# ADC16b_Pressure.net
KiCad netlist of a schematic drawn in Altium Designer
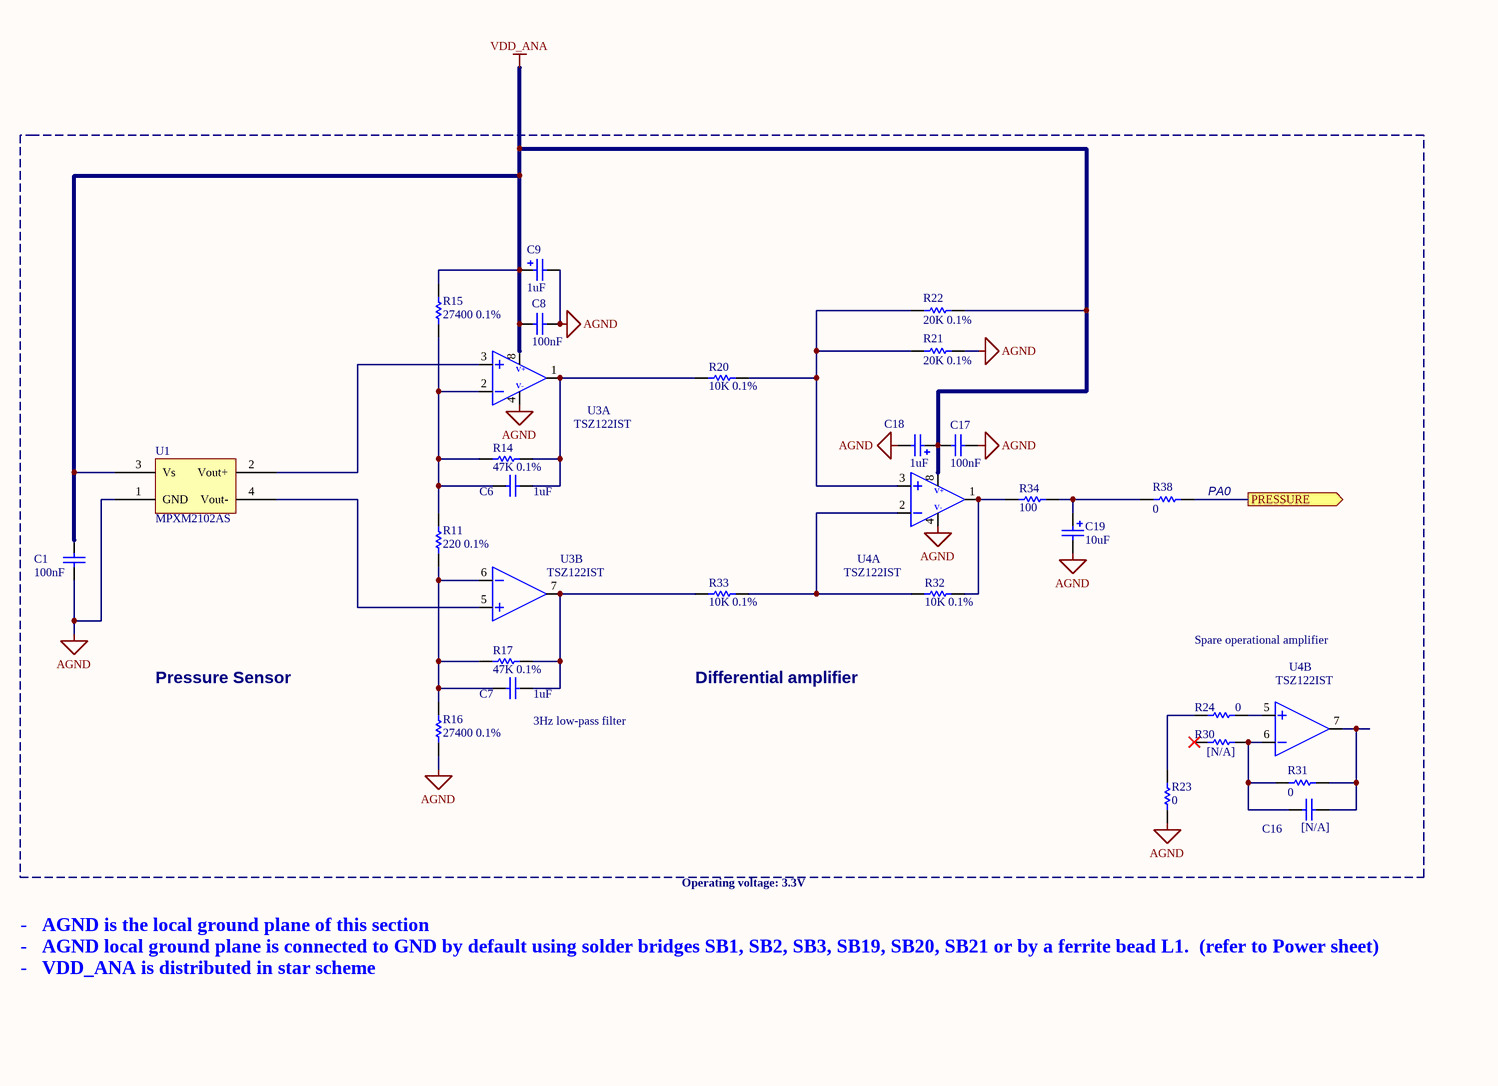
[diagram p0: ADC16b_Pressure.SchDoc]

(export (version "E")
  (design (tool "Eeschema 10.0.6"))
  (components
    (comp (ref "C1")
      (value "100nF")
      (footprint "0402C")
      (description "Capacitor")
      (fields (field (name "PUBLISHER") "Altium Limited"))
      (libsource (lib "Miscellaneous Devices") (part "CAP"))
    )
    (comp (ref "C6")
      (value "1uF")
      (footprint "0603C")
      (description "Capacitor")
      (fields (field (name "PUBLISHER") "Altium Limited"))
      (libsource (lib "Miscellaneous Devices") (part "CAP"))
    )
    (comp (ref "C7")
      (value "1uF")
      (footprint "0603C")
      (description "Capacitor")
      (fields (field (name "PUBLISHER") "Altium Limited"))
      (libsource (lib "Miscellaneous Devices") (part "CAP"))
    )
    (comp (ref "C8")
      (value "100nF")
      (footprint "0402C")
      (description "Capacitor")
      (fields (field (name "PUBLISHER") "Altium Limited"))
      (libsource (lib "Miscellaneous Devices") (part "CAP"))
    )
    (comp (ref "C9")
      (value "1uF")
      (footprint "TAN-A")
      (description "Polarized Capacitor")
      (fields (field (name "PUBLISHER") "Altium Limited"))
      (libsource (lib "Miscellaneous Devices") (part "Cap Pol1"))
    )
    (comp (ref "C16")
      (value "[N/A]")
      (footprint "0603C")
      (description "Capacitor")
      (fields (field (name "PUBLISHER") "Altium Limited"))
      (libsource (lib "Miscellaneous Devices") (part "cap"))
    )
    (comp (ref "C17")
      (value "100nF")
      (footprint "0402C")
      (description "Capacitor")
      (fields (field (name "PUBLISHER") "Altium Limited"))
      (libsource (lib "Miscellaneous Devices") (part "CAP"))
    )
    (comp (ref "C18")
      (value "1uF")
      (footprint "TAN-A")
      (description "Polarized Capacitor")
      (fields (field (name "PUBLISHER") "Altium Limited"))
      (libsource (lib "Miscellaneous Devices") (part "Cap Pol1"))
    )
    (comp (ref "C19")
      (value "10uF")
      (footprint "TAN-A")
      (description "Polarized Capacitor (Radial)")
      (fields (field (name "PUBLISHER") "Altium Limited"))
      (libsource (lib "Miscellaneous Devices") (part "Cap Pol1"))
    )
    (comp (ref "R11")
      (value "220 0.1%")
      (footprint "0603R")
      (description "Resistor")
      (fields (field (name "PUBLISHER") "Altium Limited"))
      (libsource (lib "Miscellaneous Devices") (part "Res1"))
    )
    (comp (ref "R14")
      (value "47K 0.1%")
      (footprint "0603R")
      (description "Resistor")
      (fields (field (name "PUBLISHER") "Altium Limited"))
      (libsource (lib "Miscellaneous Devices") (part "Res1"))
    )
    (comp (ref "R15")
      (value "27400 0.1%")
      (footprint "0603R")
      (description "Resistor")
      (fields (field (name "PUBLISHER") "Altium Limited"))
      (libsource (lib "Miscellaneous Devices") (part "Res1"))
    )
    (comp (ref "R16")
      (value "27400 0.1%")
      (footprint "0603R")
      (description "Resistor")
      (fields (field (name "PUBLISHER") "Altium Limited"))
      (libsource (lib "Miscellaneous Devices") (part "Res1"))
    )
    (comp (ref "R17")
      (value "47K 0.1%")
      (footprint "0603R")
      (description "Resistor")
      (fields (field (name "PUBLISHER") "Altium Limited"))
      (libsource (lib "Miscellaneous Devices") (part "Res1"))
    )
    (comp (ref "R20")
      (value "10K 0.1%")
      (footprint "0603R")
      (description "Resistor")
      (fields (field (name "PUBLISHER") "Altium Limited"))
      (libsource (lib "Miscellaneous Devices") (part "Res1"))
    )
    (comp (ref "R21")
      (value "20K 0.1%")
      (footprint "0603R")
      (description "Resistor")
      (fields (field (name "PUBLISHER") "Altium Limited"))
      (libsource (lib "Miscellaneous Devices") (part "Res1"))
    )
    (comp (ref "R22")
      (value "20K 0.1%")
      (footprint "0603R")
      (description "Resistor")
      (fields (field (name "PUBLISHER") "Altium Limited"))
      (libsource (lib "Miscellaneous Devices") (part "Res1"))
    )
    (comp (ref "R23")
      (value "0")
      (footprint "0603R")
      (description "Resistor")
      (fields (field (name "PUBLISHER") "Altium Limited"))
      (libsource (lib "Miscellaneous Devices") (part "Res1"))
    )
    (comp (ref "R24")
      (value "0")
      (footprint "0603R")
      (description "Resistor")
      (fields (field (name "PUBLISHER") "Altium Limited"))
      (libsource (lib "Miscellaneous Devices") (part "Res1"))
    )
    (comp (ref "R30")
      (value "[N/A]")
      (footprint "0603R")
      (description "Resistor")
      (fields (field (name "PUBLISHER") "Altium Limited"))
      (libsource (lib "Miscellaneous Devices") (part "Res1"))
    )
    (comp (ref "R31")
      (value "0")
      (footprint "0603R")
      (description "Resistor")
      (fields (field (name "PUBLISHER") "Altium Limited"))
      (libsource (lib "Miscellaneous Devices") (part "Res1"))
    )
    (comp (ref "R32")
      (value "10K 0.1%")
      (footprint "0603R")
      (description "Resistor")
      (fields (field (name "PUBLISHER") "Altium Limited"))
      (libsource (lib "Miscellaneous Devices") (part "Res1"))
    )
    (comp (ref "R33")
      (value "10K 0.1%")
      (footprint "0603R")
      (description "Resistor")
      (fields (field (name "PUBLISHER") "Altium Limited"))
      (libsource (lib "Miscellaneous Devices") (part "Res1"))
    )
    (comp (ref "R34")
      (value "100")
      (footprint "0402R")
      (description "Resistor")
      (fields (field (name "PUBLISHER") "Altium Limited"))
      (libsource (lib "Miscellaneous Devices") (part "Res1"))
    )
    (comp (ref "R38")
      (value "0")
      (footprint "0603R")
      (description "Resistor")
      (fields (field (name "PUBLISHER") "Altium Limited"))
      (libsource (lib "Miscellaneous Devices") (part "Res1"))
    )
    (comp (ref "U1")
      (value "MPXM2102AS")
      (footprint "SENSOR_MPXM2102AS")
      (libsource (lib "MB988") (part "MPX2102"))
    )
    (comp (ref "U3")
      (value "TSZ122IST")
      (footprint "MSOP8_0R65_3X4R9")
      (libsource (lib "") (part "AOP-8PINS_1"))
    )
    (comp (ref "U4")
      (value "TSZ122IST")
      (footprint "MSOP8_0R65_3X4R9")
      (libsource (lib "Lib_stella") (part "AOP-8PINS"))
    )
  )
  (nets
    (net (code "1") (name "/PRESSURE") (class "Default")
      (node (ref "R38") (pin "2") (pinfunction "2_2") (pintype "passive"))
    )
    (net (code "2") (name "AGND") (class "Default")
      (node (ref "C1") (pin "1") (pinfunction "1_1") (pintype "passive"))
      (node (ref "C17") (pin "1") (pinfunction "1_1") (pintype "passive"))
      (node (ref "C18") (pin "2") (pinfunction "2_2") (pintype "passive"))
      (node (ref "C19") (pin "2") (pinfunction "2_2") (pintype "passive"))
      (node (ref "C8") (pin "1") (pinfunction "1_1") (pintype "passive"))
      (node (ref "C9") (pin "2") (pinfunction "2_2") (pintype "passive"))
      (node (ref "R16") (pin "2") (pinfunction "2_2") (pintype "passive"))
      (node (ref "R21") (pin "2") (pinfunction "2_2") (pintype "passive"))
      (node (ref "R23") (pin "2") (pinfunction "2_2") (pintype "passive"))
      (node (ref "U1") (pin "1") (pinfunction "GND_1") (pintype "passive"))
      (node (ref "U3") (pin "4") (pintype "passive"))
      (node (ref "U4") (pin "4") (pintype "passive"))
    )
    (net (code "3") (name "Net-(C6-Pad1)") (class "Default")
      (node (ref "C6") (pin "1") (pinfunction "1_1") (pintype "passive"))
      (node (ref "R11") (pin "1") (pinfunction "1_1") (pintype "passive"))
      (node (ref "R14") (pin "2") (pinfunction "2_2") (pintype "passive"))
      (node (ref "R15") (pin "2") (pinfunction "2_2") (pintype "passive"))
      (node (ref "U3") (pin "2") (pintype "passive"))
    )
    (net (code "4") (name "Net-(C6-Pad2)") (class "Default")
      (node (ref "C6") (pin "2") (pinfunction "2_2") (pintype "passive"))
      (node (ref "R14") (pin "1") (pinfunction "1_1") (pintype "passive"))
      (node (ref "R20") (pin "2") (pinfunction "2_2") (pintype "passive"))
      (node (ref "U3") (pin "1") (pintype "passive"))
    )
    (net (code "5") (name "Net-(C7-Pad1)") (class "Default")
      (node (ref "C7") (pin "1") (pinfunction "1_1") (pintype "passive"))
      (node (ref "R11") (pin "2") (pinfunction "2_2") (pintype "passive"))
      (node (ref "R16") (pin "1") (pinfunction "1_1") (pintype "passive"))
      (node (ref "R17") (pin "2") (pinfunction "2_2") (pintype "passive"))
      (node (ref "U3") (pin "6") (pintype "passive"))
    )
    (net (code "6") (name "Net-(C7-Pad2)") (class "Default")
      (node (ref "C7") (pin "2") (pinfunction "2_2") (pintype "passive"))
      (node (ref "R17") (pin "1") (pinfunction "1_1") (pintype "passive"))
      (node (ref "R33") (pin "2") (pinfunction "2_2") (pintype "passive"))
      (node (ref "U3") (pin "7") (pintype "passive"))
    )
    (net (code "7") (name "Net-(C16-Pad1)") (class "Default")
      (node (ref "C16") (pin "1") (pinfunction "1_1") (pintype "passive"))
      (node (ref "R31") (pin "1") (pinfunction "1_1") (pintype "passive"))
      (node (ref "U4") (pin "7") (pintype "passive"))
    )
    (net (code "8") (name "Net-(C16-Pad2)") (class "Default")
      (node (ref "C16") (pin "2") (pinfunction "2_2") (pintype "passive"))
      (node (ref "R30") (pin "1") (pinfunction "1_1") (pintype "passive"))
      (node (ref "R31") (pin "2") (pinfunction "2_2") (pintype "passive"))
      (node (ref "U4") (pin "6") (pintype "passive"))
    )
    (net (code "9") (name "Net-(C19-Pad1)") (class "Default")
      (node (ref "C19") (pin "1") (pinfunction "1_1") (pintype "passive"))
      (node (ref "R34") (pin "1") (pinfunction "1_1") (pintype "passive"))
      (node (ref "R38") (pin "1") (pinfunction "1_1") (pintype "passive"))
    )
    (net (code "10") (name "Net-(R20-Pad1)") (class "Default")
      (node (ref "R20") (pin "1") (pinfunction "1_1") (pintype "passive"))
      (node (ref "R21") (pin "1") (pinfunction "1_1") (pintype "passive"))
      (node (ref "R22") (pin "1") (pinfunction "1_1") (pintype "passive"))
      (node (ref "U4") (pin "3") (pintype "passive"))
    )
    (net (code "11") (name "Net-(R23-Pad1)") (class "Default")
      (node (ref "R23") (pin "1") (pinfunction "1_1") (pintype "passive"))
      (node (ref "R24") (pin "2") (pinfunction "2_2") (pintype "passive"))
    )
    (net (code "12") (name "Net-(R24-Pad1)") (class "Default")
      (node (ref "R24") (pin "1") (pinfunction "1_1") (pintype "passive"))
      (node (ref "U4") (pin "5") (pintype "passive"))
    )
    (net (code "13") (name "Net-(R32-Pad1)") (class "Default")
      (node (ref "R32") (pin "1") (pinfunction "1_1") (pintype "passive"))
      (node (ref "R34") (pin "2") (pinfunction "2_2") (pintype "passive"))
      (node (ref "U4") (pin "1") (pintype "passive"))
    )
    (net (code "14") (name "Net-(R32-Pad2)") (class "Default")
      (node (ref "R32") (pin "2") (pinfunction "2_2") (pintype "passive"))
      (node (ref "R33") (pin "1") (pinfunction "1_1") (pintype "passive"))
      (node (ref "U4") (pin "2") (pintype "passive"))
    )
    (net (code "15") (name "Net-(U1-Vout+)") (class "Default")
      (node (ref "U1") (pin "2") (pinfunction "Vout+_2") (pintype "passive"))
      (node (ref "U3") (pin "3") (pintype "passive"))
    )
    (net (code "16") (name "Net-(U1-Vout-)") (class "Default")
      (node (ref "U1") (pin "4") (pinfunction "Vout-_4") (pintype "passive"))
      (node (ref "U3") (pin "5") (pintype "passive"))
    )
    (net (code "17") (name "VDD_ANA") (class "Default")
      (node (ref "C1") (pin "2") (pinfunction "2_2") (pintype "passive"))
      (node (ref "C17") (pin "2") (pinfunction "2_2") (pintype "passive"))
      (node (ref "C18") (pin "1") (pinfunction "1_1") (pintype "passive"))
      (node (ref "C8") (pin "2") (pinfunction "2_2") (pintype "passive"))
      (node (ref "C9") (pin "1") (pinfunction "1_1") (pintype "passive"))
      (node (ref "R15") (pin "1") (pinfunction "1_1") (pintype "passive"))
      (node (ref "R22") (pin "2") (pinfunction "2_2") (pintype "passive"))
      (node (ref "U1") (pin "3") (pinfunction "Vs_3") (pintype "passive"))
      (node (ref "U3") (pin "8") (pintype "passive"))
      (node (ref "U4") (pin "8") (pintype "passive"))
    )
    (net (code "18") (name "unconnected-(R30-Pad2)") (class "Default")
      (node (ref "R30") (pin "2") (pinfunction "2_2") (pintype "passive+no_connect"))
    )
  )
)
